# SCH_EEPROM-Breakout-Board_2026-05-17.net
KiCad netlist of a schematic drawn in EasyEDA
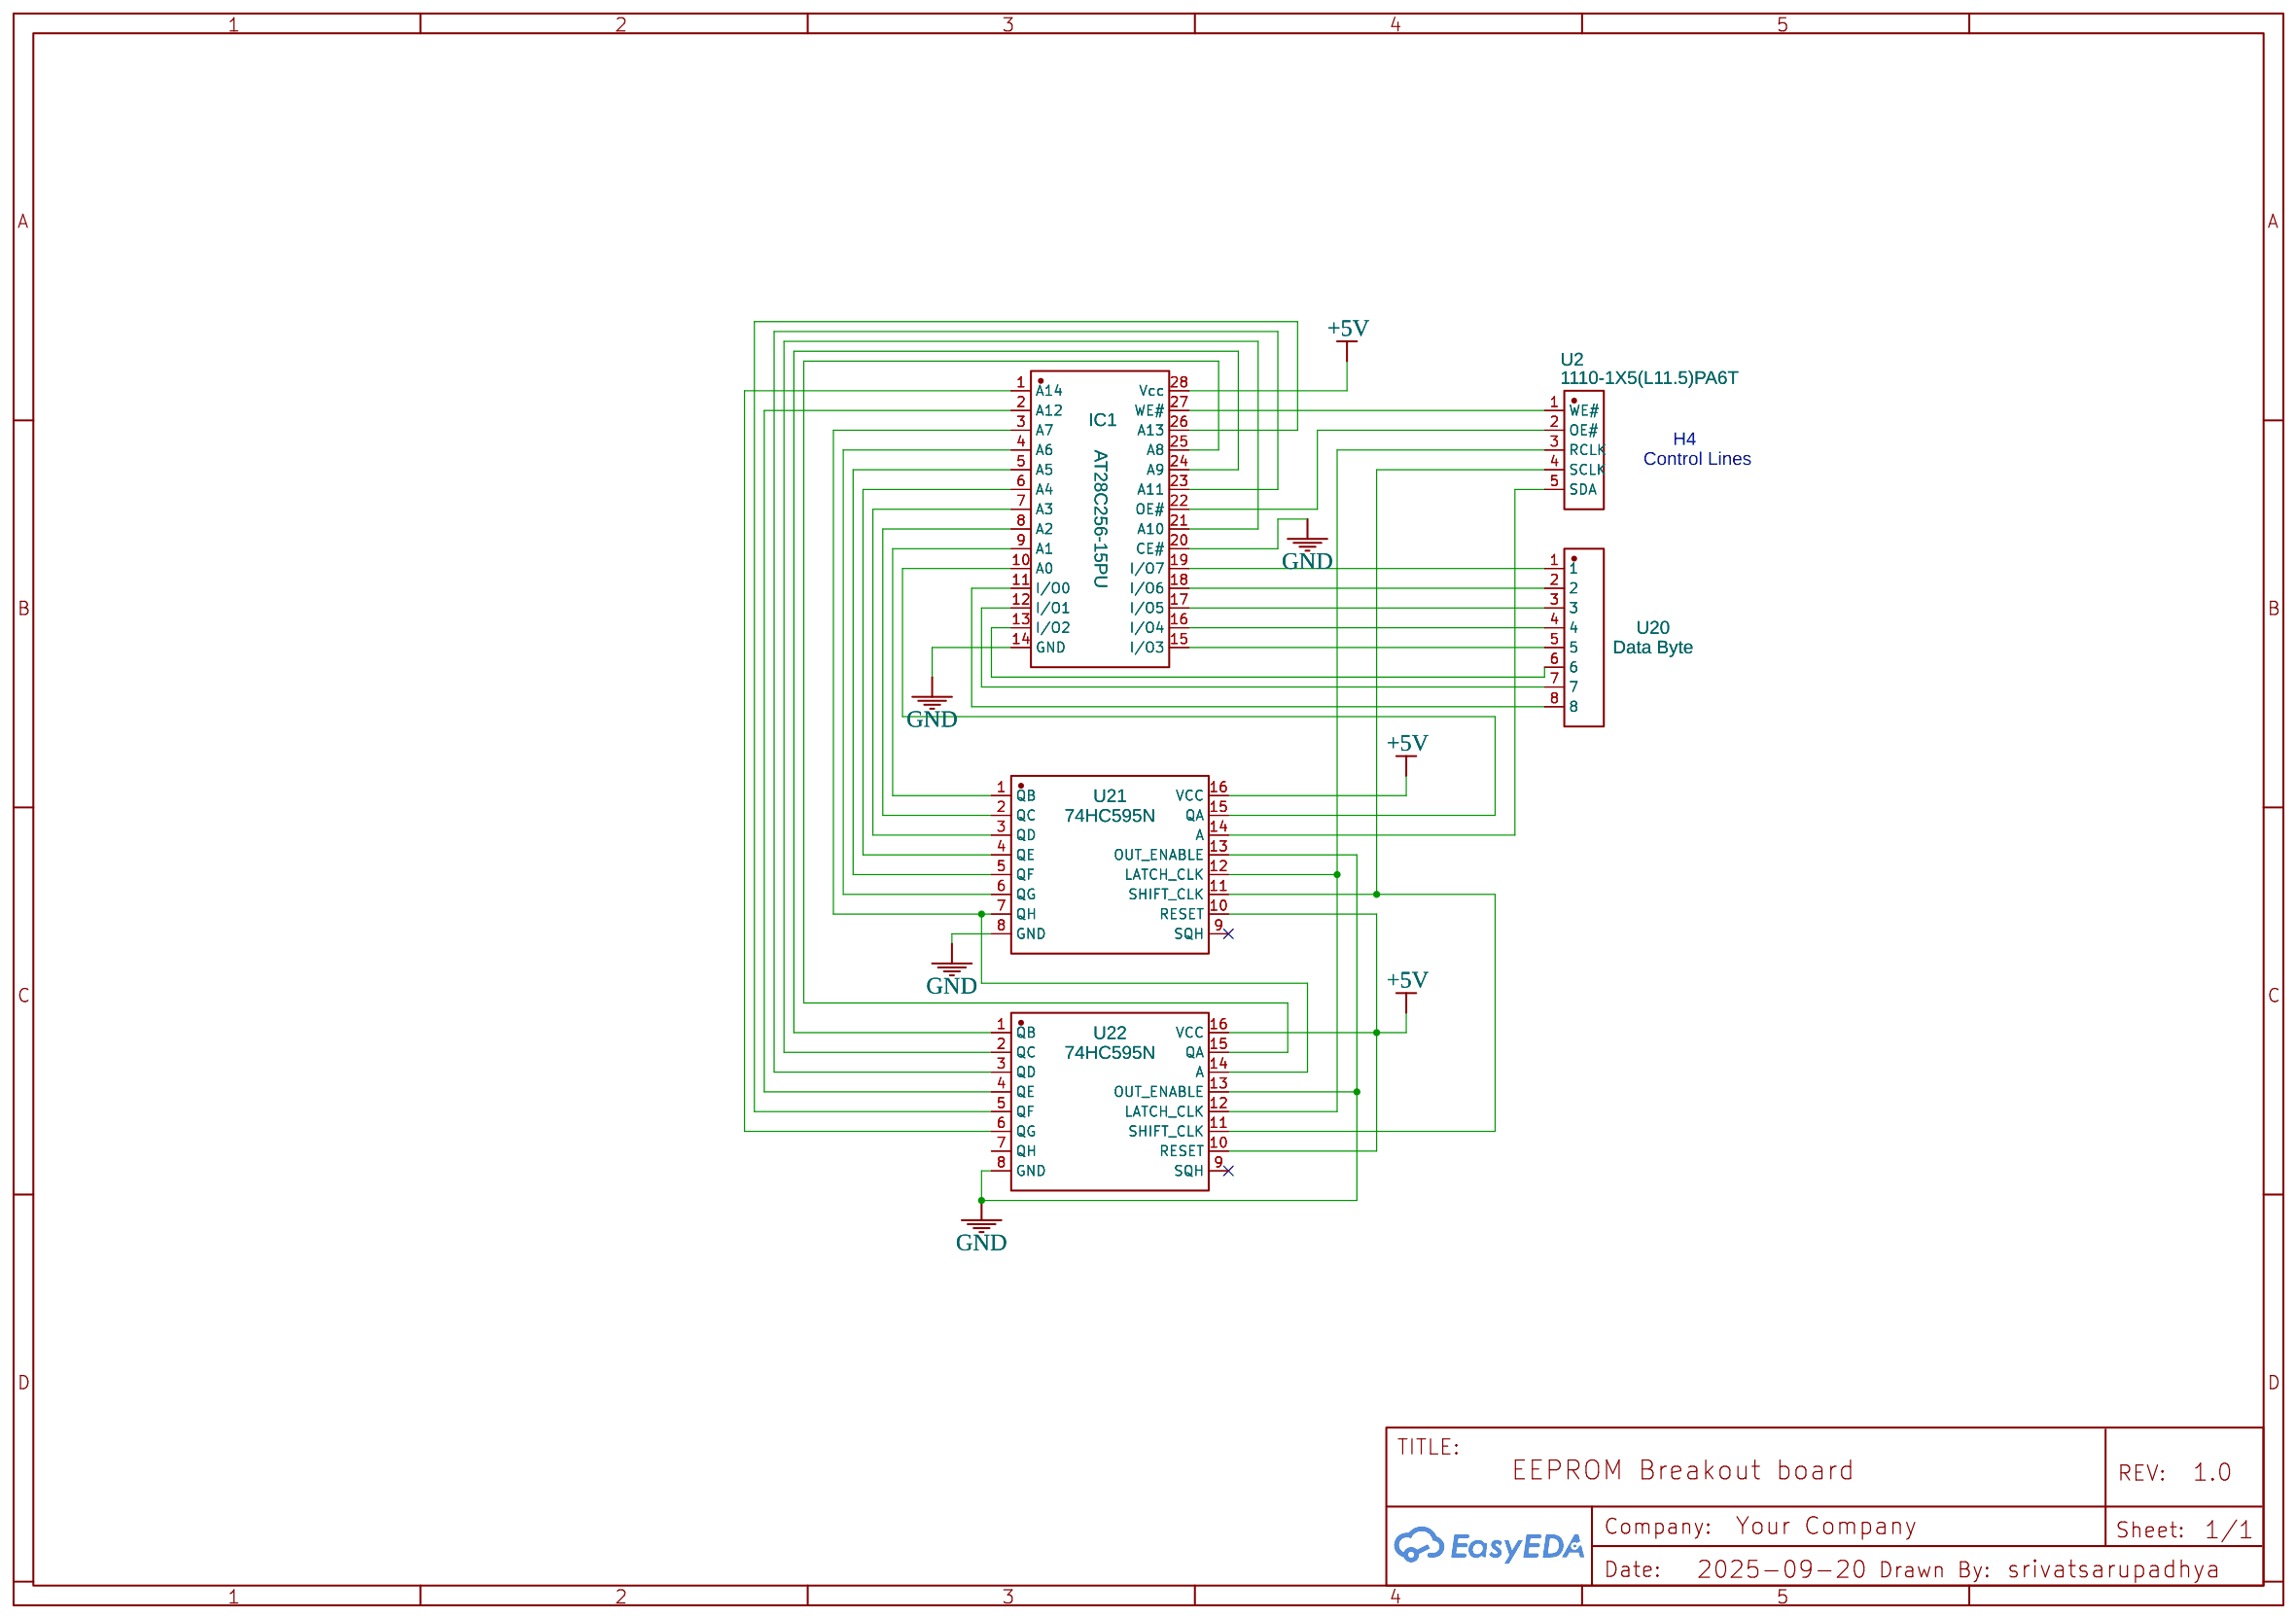
[diagram p0: schematic sheet]

(export (version "E")
  (design (tool "Eeschema 10.0.6"))
  (components
    (comp (ref "IC1")
      (value "AT28C256-15PU")
      (fields (field (name "Manufacturer") "MICROCHIP(美国微芯)"))
      (libsource (lib "") (part "AT28C256-15PU"))
    )
    (comp (ref "U2")
      (value "1110-1X5(L11.5)PA6T")
      (fields
        (field (name "Manufacturer Part") "1110-1x5(L11.5)PA6T")
        (field (name "Manufacturer") "CST(永丰盈)")
      )
      (libsource (lib "") (part "1110-1X5(L11.5)PA6T"))
    )
    (comp (ref "U20")
      (value "Data Byte")
      (fields (field (name "Manufacturer Part") "2.54-1*8") (field (name "Manufacturer") "ZHOURI(洲日)"))
      (libsource (lib "") (part "2.54-1*8"))
    )
    (comp (ref "U21")
      (value "74HC595N")
      (fields (field (name "Manufacturer") "HTC"))
      (libsource (lib "") (part "74HC595N_C669328"))
    )
    (comp (ref "U22")
      (value "74HC595N")
      (fields (field (name "Manufacturer") "HTC"))
      (libsource (lib "") (part "74HC595N_C669328"))
    )
  )
  (nets
    (net (code "1") (name "+5V") (class "Default")
      (node (ref "IC1") (pin "28") (pinfunction "Vcc_28") (pintype "unspecified"))
      (node (ref "U21") (pin "10") (pinfunction "RESET_10") (pintype "unspecified"))
      (node (ref "U21") (pin "16") (pinfunction "VCC_16") (pintype "unspecified"))
      (node (ref "U22") (pin "10") (pinfunction "RESET_10") (pintype "unspecified"))
      (node (ref "U22") (pin "16") (pinfunction "VCC_16") (pintype "unspecified"))
    )
    (net (code "2") (name "GND") (class "Default")
      (node (ref "IC1") (pin "14") (pinfunction "GND_14") (pintype "unspecified"))
      (node (ref "IC1") (pin "20") (pinfunction "CE#_20") (pintype "unspecified"))
      (node (ref "U21") (pin "13") (pinfunction "OUT_ENABLE_13") (pintype "unspecified"))
      (node (ref "U21") (pin "8") (pinfunction "GND_8") (pintype "unspecified"))
      (node (ref "U22") (pin "13") (pinfunction "OUT_ENABLE_13") (pintype "unspecified"))
      (node (ref "U22") (pin "8") (pinfunction "GND_8") (pintype "unspecified"))
    )
    (net (code "3") (name "Net-(IC1-A0)") (class "Default")
      (node (ref "IC1") (pin "10") (pinfunction "A0_10") (pintype "unspecified"))
      (node (ref "U21") (pin "15") (pinfunction "QA_15") (pintype "unspecified"))
    )
    (net (code "4") (name "Net-(IC1-A1)") (class "Default")
      (node (ref "IC1") (pin "9") (pinfunction "A1_9") (pintype "unspecified"))
      (node (ref "U21") (pin "1") (pinfunction "QB_1") (pintype "unspecified"))
    )
    (net (code "5") (name "Net-(IC1-A2)") (class "Default")
      (node (ref "IC1") (pin "8") (pinfunction "A2_8") (pintype "unspecified"))
      (node (ref "U21") (pin "2") (pinfunction "QC_2") (pintype "unspecified"))
    )
    (net (code "6") (name "Net-(IC1-A3)") (class "Default")
      (node (ref "IC1") (pin "7") (pinfunction "A3_7") (pintype "unspecified"))
      (node (ref "U21") (pin "3") (pinfunction "QD_3") (pintype "unspecified"))
    )
    (net (code "7") (name "Net-(IC1-A4)") (class "Default")
      (node (ref "IC1") (pin "6") (pinfunction "A4_6") (pintype "unspecified"))
      (node (ref "U21") (pin "4") (pinfunction "QE_4") (pintype "unspecified"))
    )
    (net (code "8") (name "Net-(IC1-A5)") (class "Default")
      (node (ref "IC1") (pin "5") (pinfunction "A5_5") (pintype "unspecified"))
      (node (ref "U21") (pin "5") (pinfunction "QF_5") (pintype "unspecified"))
    )
    (net (code "9") (name "Net-(IC1-A6)") (class "Default")
      (node (ref "IC1") (pin "4") (pinfunction "A6_4") (pintype "unspecified"))
      (node (ref "U21") (pin "6") (pinfunction "QG_6") (pintype "unspecified"))
    )
    (net (code "10") (name "Net-(IC1-A7)") (class "Default")
      (node (ref "IC1") (pin "3") (pinfunction "A7_3") (pintype "unspecified"))
      (node (ref "U21") (pin "7") (pinfunction "QH_7") (pintype "unspecified"))
      (node (ref "U22") (pin "14") (pinfunction "A_14") (pintype "unspecified"))
    )
    (net (code "11") (name "Net-(IC1-A8)") (class "Default")
      (node (ref "IC1") (pin "25") (pinfunction "A8_25") (pintype "unspecified"))
      (node (ref "U22") (pin "15") (pinfunction "QA_15") (pintype "unspecified"))
    )
    (net (code "12") (name "Net-(IC1-A9)") (class "Default")
      (node (ref "IC1") (pin "24") (pinfunction "A9_24") (pintype "unspecified"))
      (node (ref "U22") (pin "1") (pinfunction "QB_1") (pintype "unspecified"))
    )
    (net (code "13") (name "Net-(IC1-A10)") (class "Default")
      (node (ref "IC1") (pin "21") (pinfunction "A10_21") (pintype "unspecified"))
      (node (ref "U22") (pin "2") (pinfunction "QC_2") (pintype "unspecified"))
    )
    (net (code "14") (name "Net-(IC1-A11)") (class "Default")
      (node (ref "IC1") (pin "23") (pinfunction "A11_23") (pintype "unspecified"))
      (node (ref "U22") (pin "3") (pinfunction "QD_3") (pintype "unspecified"))
    )
    (net (code "15") (name "Net-(IC1-A12)") (class "Default")
      (node (ref "IC1") (pin "2") (pinfunction "A12_2") (pintype "unspecified"))
      (node (ref "U22") (pin "4") (pinfunction "QE_4") (pintype "unspecified"))
    )
    (net (code "16") (name "Net-(IC1-A13)") (class "Default")
      (node (ref "IC1") (pin "26") (pinfunction "A13_26") (pintype "unspecified"))
      (node (ref "U22") (pin "5") (pinfunction "QF_5") (pintype "unspecified"))
    )
    (net (code "17") (name "Net-(IC1-A14)") (class "Default")
      (node (ref "IC1") (pin "1") (pinfunction "A14_1") (pintype "unspecified"))
      (node (ref "U22") (pin "6") (pinfunction "QG_6") (pintype "unspecified"))
    )
    (net (code "18") (name "Net-(IC1-I{slash}O0)") (class "Default")
      (node (ref "IC1") (pin "11") (pinfunction "I/O0_11") (pintype "unspecified"))
      (node (ref "U20") (pin "8") (pinfunction "8_8") (pintype "unspecified"))
    )
    (net (code "19") (name "Net-(IC1-I{slash}O1)") (class "Default")
      (node (ref "IC1") (pin "12") (pinfunction "I/O1_12") (pintype "unspecified"))
      (node (ref "U20") (pin "7") (pinfunction "7_7") (pintype "unspecified"))
    )
    (net (code "20") (name "Net-(IC1-I{slash}O2)") (class "Default")
      (node (ref "IC1") (pin "13") (pinfunction "I/O2_13") (pintype "unspecified"))
      (node (ref "U20") (pin "6") (pinfunction "6_6") (pintype "unspecified"))
    )
    (net (code "21") (name "Net-(IC1-I{slash}O3)") (class "Default")
      (node (ref "IC1") (pin "15") (pinfunction "I/O3_15") (pintype "unspecified"))
      (node (ref "U20") (pin "5") (pinfunction "5_5") (pintype "unspecified"))
    )
    (net (code "22") (name "Net-(IC1-I{slash}O4)") (class "Default")
      (node (ref "IC1") (pin "16") (pinfunction "I/O4_16") (pintype "unspecified"))
      (node (ref "U20") (pin "4") (pinfunction "4_4") (pintype "unspecified"))
    )
    (net (code "23") (name "Net-(IC1-I{slash}O5)") (class "Default")
      (node (ref "IC1") (pin "17") (pinfunction "I/O5_17") (pintype "unspecified"))
      (node (ref "U20") (pin "3") (pinfunction "3_3") (pintype "unspecified"))
    )
    (net (code "24") (name "Net-(IC1-I{slash}O6)") (class "Default")
      (node (ref "IC1") (pin "18") (pinfunction "I/O6_18") (pintype "unspecified"))
      (node (ref "U20") (pin "2") (pinfunction "2_2") (pintype "unspecified"))
    )
    (net (code "25") (name "Net-(IC1-I{slash}O7)") (class "Default")
      (node (ref "IC1") (pin "19") (pinfunction "I/O7_19") (pintype "unspecified"))
      (node (ref "U20") (pin "1") (pinfunction "1_1") (pintype "unspecified"))
    )
    (net (code "26") (name "Net-(IC1-OE#)") (class "Default")
      (node (ref "IC1") (pin "22") (pinfunction "OE#_22") (pintype "unspecified"))
      (node (ref "U2") (pin "2") (pinfunction "OE#_2") (pintype "unspecified"))
    )
    (net (code "27") (name "Net-(IC1-WE#)") (class "Default")
      (node (ref "IC1") (pin "27") (pinfunction "WE#_27") (pintype "unspecified"))
      (node (ref "U2") (pin "1") (pinfunction "WE#_1") (pintype "unspecified"))
    )
    (net (code "28") (name "Net-(U2-RCLK)") (class "Default")
      (node (ref "U2") (pin "3") (pinfunction "RCLK_3") (pintype "unspecified"))
      (node (ref "U21") (pin "12") (pinfunction "LATCH_CLK_12") (pintype "unspecified"))
      (node (ref "U22") (pin "12") (pinfunction "LATCH_CLK_12") (pintype "unspecified"))
    )
    (net (code "29") (name "Net-(U2-SCLK)") (class "Default")
      (node (ref "U2") (pin "4") (pinfunction "SCLK_4") (pintype "unspecified"))
      (node (ref "U21") (pin "11") (pinfunction "SHIFT_CLK_11") (pintype "unspecified"))
      (node (ref "U22") (pin "11") (pinfunction "SHIFT_CLK_11") (pintype "unspecified"))
    )
    (net (code "30") (name "Net-(U2-SDA)") (class "Default")
      (node (ref "U2") (pin "5") (pinfunction "SDA_5") (pintype "unspecified"))
      (node (ref "U21") (pin "14") (pinfunction "A_14") (pintype "unspecified"))
    )
    (net (code "31") (name "unconnected-(U21-SQH-Pad9)") (class "Default")
      (node (ref "U21") (pin "9") (pinfunction "SQH_9") (pintype "unspecified+no_connect"))
    )
    (net (code "32") (name "unconnected-(U22-QH-Pad7)") (class "Default")
      (node (ref "U22") (pin "7") (pinfunction "QH_7") (pintype "unspecified"))
    )
    (net (code "33") (name "unconnected-(U22-SQH-Pad9)") (class "Default")
      (node (ref "U22") (pin "9") (pinfunction "SQH_9") (pintype "unspecified+no_connect"))
    )
  )
)
